# EIT_Teensy_VCCS.net
KiCad netlist of a schematic drawn in Altium Designer
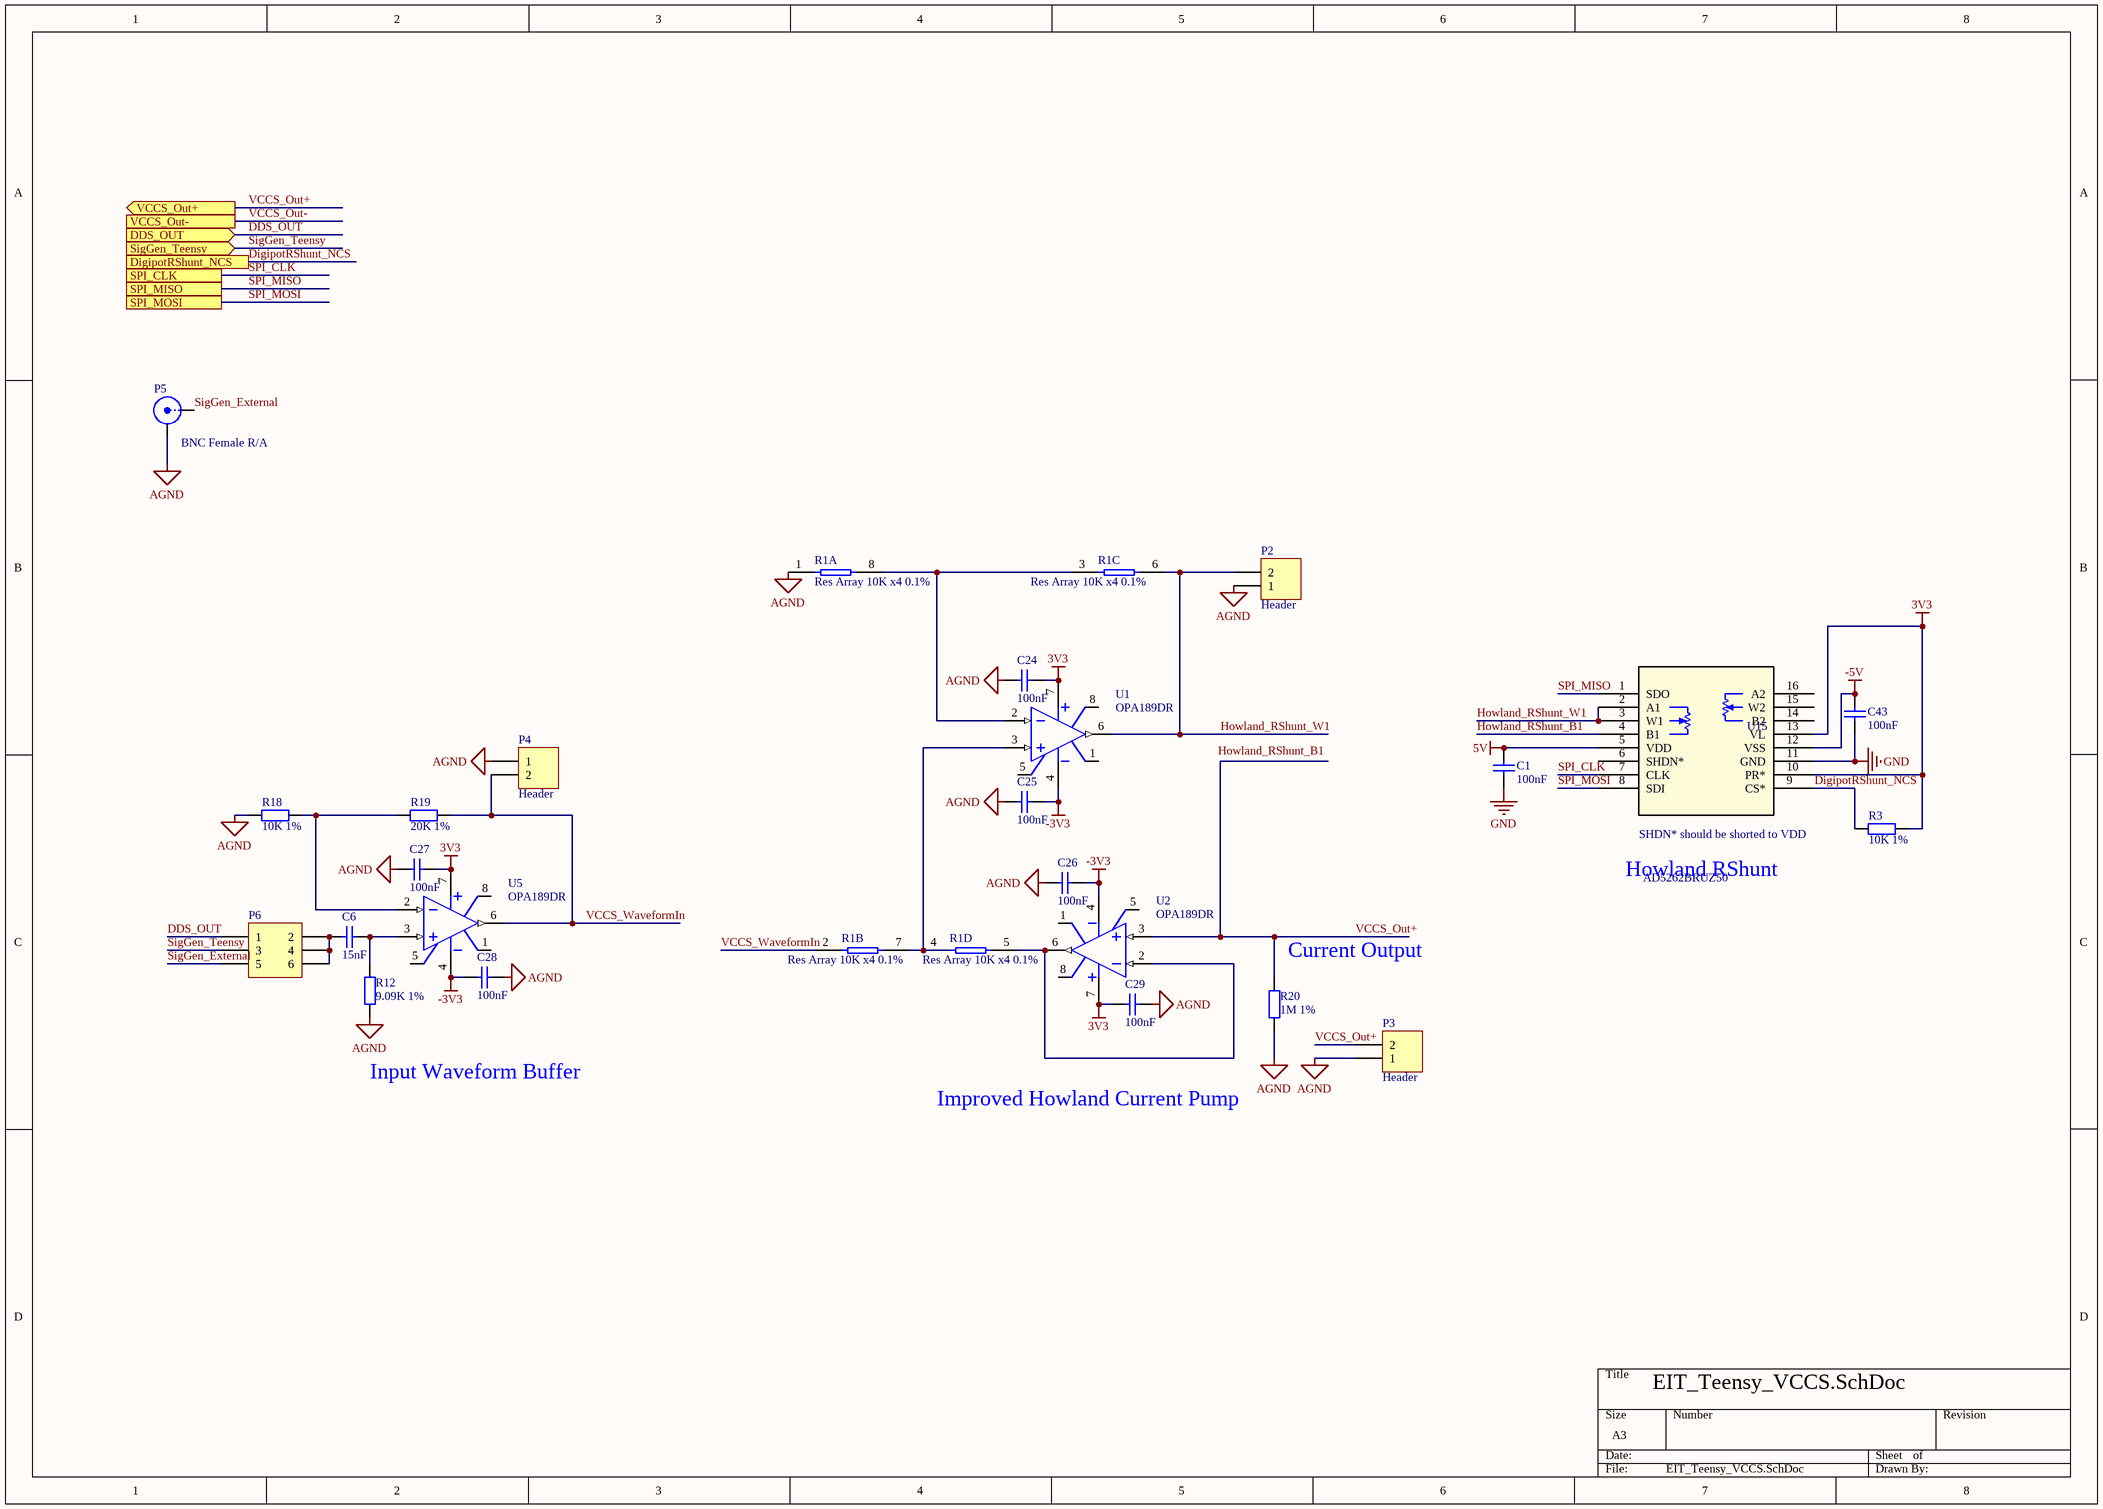
[diagram p0: EIT_Teensy_VCCS.SchDoc]

(export (version "E")
  (design (tool "Eeschema 10.0.6"))
  (components
    (comp (ref "C1")
      (value "100nF")
      (footprint "0603 CAP")
      (description "Multi Layer Ceramic Capacitor (MLCC) / Cap Ceramic 0.1uF 50V X7R 10% Pad SMD 0603 125°C T/R")
      (fields
        (field (name "MANUFACTURER") "Samsung")
        (field (name "MANUFACTURER PART NUMBER") "CL10B104KB8NNNC")
      )
      (libsource (lib "EitLib") (part "Cap 0603 100nF 10% 50V"))
    )
    (comp (ref "C6")
      (value "15nF")
      (footprint "0603 CAP")
      (description "Cap Ceramic 0.015uF 50V X7R 10% SMD 0603 125C T/R")
      (fields
        (field (name "MANUFACTURER") "Yageo")
        (field (name "MANUFACTURER PART NUMBER") "CC0603KRX7R9BB153")
      )
      (libsource (lib "EitLib") (part "Cap 0603 15nF 10% 50V"))
    )
    (comp (ref "C24")
      (value "100nF")
      (footprint "0603 CAP")
      (description "Multi Layer Ceramic Capacitor (MLCC) / Cap Ceramic 0.1uF 50V X7R 10% Pad SMD 0603 125°C T/R")
      (fields
        (field (name "MANUFACTURER") "Samsung")
        (field (name "MANUFACTURER PART NUMBER") "CL10B104KB8NNNC")
      )
      (libsource (lib "EitLib") (part "Cap 0603 100nF 10% 50V"))
    )
    (comp (ref "C25")
      (value "100nF")
      (footprint "0603 CAP")
      (description "Multi Layer Ceramic Capacitor (MLCC) / Cap Ceramic 0.1uF 50V X7R 10% Pad SMD 0603 125°C T/R")
      (fields
        (field (name "MANUFACTURER") "Samsung")
        (field (name "MANUFACTURER PART NUMBER") "CL10B104KB8NNNC")
      )
      (libsource (lib "EitLib") (part "Cap 0603 100nF 10% 50V"))
    )
    (comp (ref "C26")
      (value "100nF")
      (footprint "0603 CAP")
      (description "Multi Layer Ceramic Capacitor (MLCC) / Cap Ceramic 0.1uF 50V X7R 10% Pad SMD 0603 125°C T/R")
      (fields
        (field (name "MANUFACTURER") "Samsung")
        (field (name "MANUFACTURER PART NUMBER") "CL10B104KB8NNNC")
      )
      (libsource (lib "EitLib") (part "Cap 0603 100nF 10% 50V"))
    )
    (comp (ref "C27")
      (value "100nF")
      (footprint "0603 CAP")
      (description "Multi Layer Ceramic Capacitor (MLCC) / Cap Ceramic 0.1uF 50V X7R 10% Pad SMD 0603 125°C T/R")
      (fields
        (field (name "MANUFACTURER") "Samsung")
        (field (name "MANUFACTURER PART NUMBER") "CL10B104KB8NNNC")
      )
      (libsource (lib "EitLib") (part "Cap 0603 100nF 10% 50V"))
    )
    (comp (ref "C28")
      (value "100nF")
      (footprint "0603 CAP")
      (description "Multi Layer Ceramic Capacitor (MLCC) / Cap Ceramic 0.1uF 50V X7R 10% Pad SMD 0603 125°C T/R")
      (fields
        (field (name "MANUFACTURER") "Samsung")
        (field (name "MANUFACTURER PART NUMBER") "CL10B104KB8NNNC")
      )
      (libsource (lib "EitLib") (part "Cap 0603 100nF 10% 50V"))
    )
    (comp (ref "C29")
      (value "100nF")
      (footprint "0603 CAP")
      (description "Multi Layer Ceramic Capacitor (MLCC) / Cap Ceramic 0.1uF 50V X7R 10% Pad SMD 0603 125°C T/R")
      (fields
        (field (name "MANUFACTURER") "Samsung")
        (field (name "MANUFACTURER PART NUMBER") "CL10B104KB8NNNC")
      )
      (libsource (lib "EitLib") (part "Cap 0603 100nF 10% 50V"))
    )
    (comp (ref "C43")
      (value "100nF")
      (footprint "0603 CAP")
      (description "Multi Layer Ceramic Capacitor (MLCC) / Cap Ceramic 0.1uF 50V X7R 10% Pad SMD 0603 125°C T/R")
      (fields
        (field (name "MANUFACTURER") "Samsung")
        (field (name "MANUFACTURER PART NUMBER") "CL10B104KB8NNNC")
      )
      (libsource (lib "EitLib") (part "Cap 0603 100nF 10% 50V"))
    )
    (comp (ref "P2")
      (value "Header")
      (footprint "HEADER 2.54MM 2X1 MALE")
      (description "CONN HEADER VERT 2POS 2.54MM")
      (fields
        (field (name "MANUFACTURER") "Sullins")
        (field (name "MANUFACTURER PART NUMBER") "PRPC002SAAN-RC")
      )
      (libsource (lib "EitLib") (part "Header 2x1 2.54mm T/H Male"))
    )
    (comp (ref "P3")
      (value "Header")
      (footprint "HEADER 2.54MM 2X1 MALE")
      (description "CONN HEADER VERT 2POS 2.54MM")
      (fields
        (field (name "MANUFACTURER") "Sullins")
        (field (name "MANUFACTURER PART NUMBER") "PRPC002SAAN-RC")
      )
      (libsource (lib "EitLib") (part "Header 2x1 2.54mm T/H Male"))
    )
    (comp (ref "P4")
      (value "Header")
      (footprint "HEADER 2.54MM 2X1 MALE")
      (description "CONN HEADER VERT 2POS 2.54MM")
      (fields
        (field (name "MANUFACTURER") "Sullins")
        (field (name "MANUFACTURER PART NUMBER") "PRPC002SAAN-RC")
      )
      (libsource (lib "") (part "Header 2x1 2.54mm T/H Male_1"))
    )
    (comp (ref "P5")
      (value "BNC Female R/A")
      (footprint "BNC_RA CON")
      (description "Conn ZDC/BNC RCP 0Hz to 4GHz 50Ohm Solder RA Thru-Hole Gold Over Nickel Over Copper Individual")
      (fields
        (field (name "MANUFACTURER") "TE Connectivity")
        (field (name "MANUFACTURER PART NUMBER") "1-1337543-0")
      )
      (libsource (lib "EitLib") (part "Jack BNC Female T/H R/A TE"))
    )
    (comp (ref "P6")
      (value "Header 3X2")
      (footprint "HDR2X3 Male 2.54mm")
      (description "Header, 3-Pin, Dual row")
      (libsource (lib "EitLib") (part "Header 3X2 2.54mm Male"))
    )
    (comp (ref "R1")
      (value "Res Array 10K x4 0.1%")
      (footprint "8-SOIC")
      (fields
        (field (name "MANUFACTURER") "Vishay Dale Thin Film")
        (field (name "MANUFACTURER PART NUMBER") "ORNTA1002AT1")
        (field (name "TOLERANCE") "0.1%")
      )
      (libsource (lib "EitLib") (part "Res Array 10K x4 0.1%"))
    )
    (comp (ref "R3")
      (value "10K 1%")
      (footprint "0603 RES")
      (description "Res General Purpose Thick Film 0603 10K Ohm 1% 1/10W ±100ppm/°C Molded SMD Paper T/R")
      (fields
        (field (name "MANUFACTURER") "Yageo")
        (field (name "MANUFACTURER PART NUMBER") "RC0603FR-0710KL")
      )
      (libsource (lib "") (part "Res 0603 10K 1%_1"))
    )
    (comp (ref "R12")
      (value "9.09K 1%")
      (footprint "0603 RES")
      (description "Res Thick Film 0603 90.9K Ohm 1% 0.1W(1/10W) ±100ppm/C Epoxy SMD T/R")
      (fields
        (field (name "MANUFACTURER") "Yageo")
        (field (name "MANUFACTURER PART NUMBER") "RC0603FR-0790K9L")
      )
      (libsource (lib "EitLib") (part "Res 0603 9.09K 1%"))
    )
    (comp (ref "R18")
      (value "10K 1%")
      (footprint "0603 RES")
      (description "Res General Purpose Thick Film 0603 10K Ohm 1% 1/10W ±100ppm/°C Molded SMD Paper T/R")
      (fields
        (field (name "MANUFACTURER") "Yageo")
        (field (name "MANUFACTURER PART NUMBER") "RC0603FR-0710KL")
      )
      (libsource (lib "EitLib") (part "Res 0603 10K 1%"))
    )
    (comp (ref "R19")
      (value "20K 1%")
      (footprint "0603 RES")
      (description "Res General Purpose Thick Film 0603 20K Ohm 1% 1/10W ±100ppm/°C Molded SMD Paper T/R")
      (fields
        (field (name "MANUFACTURER") "Yageo")
        (field (name "MANUFACTURER PART NUMBER") "RC0603FR-0720KL")
      )
      (libsource (lib "EitLib") (part "Res 0603 20K 1%"))
    )
    (comp (ref "R20")
      (value "1M 1%")
      (footprint "0603 RES")
      (description "Yageo RC Series Thick Film Surface Mount Resistor 0603 Case 1M 1% 0.1W 100ppm/C")
      (fields
        (field (name "MANUFACTURER") "Yageo")
        (field (name "MANUFACTURER PART NUMBER") "RC0603FR-071ML")
      )
      (libsource (lib "EitLib") (part "Res 0603 1M 1%"))
    )
    (comp (ref "U1")
      (value "OPA189DR")
      (footprint "8-SOIC")
      (description "36V ZERO DRIFT OP-AMP")
      (fields
        (field (name "MANUFACTURER") "Texas Instruments")
        (field (name "MANUFACTURER PART NUMBER") "OPA189IDR")
      )
      (libsource (lib "EitLib") (part "OpAmp OPA189DR"))
    )
    (comp (ref "U2")
      (value "OPA189DR")
      (footprint "8-SOIC")
      (description "36V ZERO DRIFT OP-AMP")
      (fields
        (field (name "MANUFACTURER") "Texas Instruments")
        (field (name "MANUFACTURER PART NUMBER") "OPA189IDR")
      )
      (libsource (lib "EitLib") (part "OpAmp OPA189DR"))
    )
    (comp (ref "U5")
      (value "OPA189DR")
      (footprint "8-SOIC")
      (description "36V ZERO DRIFT OP-AMP")
      (fields
        (field (name "MANUFACTURER") "Texas Instruments")
        (field (name "MANUFACTURER PART NUMBER") "OPA189IDR")
      )
      (libsource (lib "EitLib") (part "OpAmp OPA189DR"))
    )
    (comp (ref "U15")
      (value "AD5262BRUZ50")
      (description "Digital Potentiometer, 2 Func, 50000ohm, 3-wire Serial Control Interface, 256 Positions, PDSO16")
      (fields (field (name "MANUFACTURER") "Analog Devices"))
      (libsource (lib "EitLib") (part "AD5262BRUZ50"))
    )
  )
  (nets
    (net (code "1") (name "-3V3") (class "Default")
      (node (ref "C25") (pin "2") (pinfunction "2_2") (pintype "passive"))
      (node (ref "C26") (pin "2") (pinfunction "2_2") (pintype "passive"))
      (node (ref "C28") (pin "1") (pinfunction "1_1") (pintype "passive"))
      (node (ref "U1") (pin "4") (pinfunction "V-_4") (pintype "power_in"))
      (node (ref "U2") (pin "4") (pinfunction "V-_4") (pintype "power_in"))
      (node (ref "U5") (pin "4") (pinfunction "V-_4") (pintype "power_in"))
    )
    (net (code "2") (name "-5V") (class "Default")
      (node (ref "C43") (pin "2") (pinfunction "2_2") (pintype "passive"))
      (node (ref "U15") (pin "12") (pinfunction "VSS_12") (pintype "power_in"))
    )
    (net (code "3") (name "/DDS_OUT") (class "Default")
      (node (ref "P6") (pin "1") (pinfunction "1_1") (pintype "passive"))
    )
    (net (code "4") (name "/DigipotRShunt_NCS") (class "Default")
      (node (ref "R3") (pin "2") (pinfunction "2_2") (pintype "passive"))
      (node (ref "U15") (pin "9") (pinfunction "CS*_9") (pintype "passive"))
    )
    (net (code "5") (name "/Howland_RShunt_B1") (class "Default")
      (node (ref "U15") (pin "4") (pinfunction "B1_4") (pintype "passive"))
    )
    (net (code "6") (name "/Howland_RShunt_W1") (class "Default")
      (node (ref "P2") (pin "2") (pinfunction "2_2") (pintype "passive"))
      (node (ref "R1") (pin "6") (pinfunction "6_6") (pintype "passive"))
      (node (ref "U1") (pin "6") (pinfunction "OUT_6") (pintype "output"))
      (node (ref "U15") (pin "2") (pinfunction "A1_2") (pintype "passive"))
      (node (ref "U15") (pin "3") (pinfunction "W1_3") (pintype "passive"))
    )
    (net (code "7") (name "/SPI_CLK") (class "Default")
      (node (ref "U15") (pin "7") (pinfunction "CLK_7") (pintype "passive"))
    )
    (net (code "8") (name "/SPI_MISO") (class "Default")
      (node (ref "U15") (pin "1") (pinfunction "SDO_1") (pintype "passive"))
    )
    (net (code "9") (name "/SPI_MOSI") (class "Default")
      (node (ref "U15") (pin "8") (pinfunction "SDI_8") (pintype "passive"))
    )
    (net (code "10") (name "/SigGen_External") (class "Default")
      (node (ref "P5") (pin "1") (pinfunction "X_1") (pintype "passive"))
      (node (ref "P6") (pin "5") (pinfunction "5_5") (pintype "passive"))
    )
    (net (code "11") (name "/SigGen_Teensy") (class "Default")
      (node (ref "P6") (pin "3") (pinfunction "3_3") (pintype "passive"))
    )
    (net (code "12") (name "/VCCS_Out+") (class "Default")
      (node (ref "P3") (pin "2") (pinfunction "2_2") (pintype "passive"))
      (node (ref "R20") (pin "1") (pinfunction "1_1") (pintype "passive"))
      (node (ref "U2") (pin "3") (pinfunction "IN+_3") (pintype "input"))
    )
    (net (code "14") (name "/VCCS_WaveformIn") (class "Default")
      (node (ref "P4") (pin "2") (pinfunction "2_2") (pintype "passive"))
      (node (ref "R1") (pin "2") (pinfunction "2_2") (pintype "passive"))
      (node (ref "R19") (pin "2") (pinfunction "2_2") (pintype "passive"))
      (node (ref "U5") (pin "6") (pinfunction "OUT_6") (pintype "output"))
    )
    (net (code "15") (name "3V3") (class "Default")
      (node (ref "C24") (pin "2") (pinfunction "2_2") (pintype "passive"))
      (node (ref "C27") (pin "2") (pinfunction "2_2") (pintype "passive"))
      (node (ref "C29") (pin "2") (pinfunction "2_2") (pintype "passive"))
      (node (ref "R3") (pin "1") (pinfunction "1_1") (pintype "passive"))
      (node (ref "U1") (pin "7") (pinfunction "V+_7") (pintype "power_in"))
      (node (ref "U15") (pin "10") (pinfunction "PR*_10") (pintype "passive"))
      (node (ref "U15") (pin "13") (pinfunction "VL_13") (pintype "power_in"))
      (node (ref "U2") (pin "7") (pinfunction "V+_7") (pintype "power_in"))
      (node (ref "U5") (pin "7") (pinfunction "V+_7") (pintype "power_in"))
    )
    (net (code "16") (name "5V") (class "Default")
      (node (ref "C1") (pin "2") (pinfunction "2_2") (pintype "passive"))
      (node (ref "U15") (pin "5") (pinfunction "VDD_5") (pintype "power_in"))
    )
    (net (code "17") (name "AGND") (class "Default")
      (node (ref "C24") (pin "1") (pinfunction "1_1") (pintype "passive"))
      (node (ref "C25") (pin "1") (pinfunction "1_1") (pintype "passive"))
      (node (ref "C26") (pin "1") (pinfunction "1_1") (pintype "passive"))
      (node (ref "C27") (pin "1") (pinfunction "1_1") (pintype "passive"))
      (node (ref "C28") (pin "2") (pinfunction "2_2") (pintype "passive"))
      (node (ref "C29") (pin "1") (pinfunction "1_1") (pintype "passive"))
      (node (ref "P2") (pin "1") (pinfunction "1_1") (pintype "passive"))
      (node (ref "P3") (pin "1") (pinfunction "1_1") (pintype "passive"))
      (node (ref "P4") (pin "1") (pinfunction "1_1") (pintype "passive"))
      (node (ref "P5") (pin "2") (pinfunction "Y_2") (pintype "passive"))
      (node (ref "R1") (pin "1") (pinfunction "1_1") (pintype "passive"))
      (node (ref "R12") (pin "1") (pinfunction "1_1") (pintype "passive"))
      (node (ref "R18") (pin "1") (pinfunction "1_1") (pintype "passive"))
      (node (ref "R20") (pin "2") (pinfunction "2_2") (pintype "passive"))
    )
    (net (code "18") (name "GND") (class "Default")
      (node (ref "C1") (pin "1") (pinfunction "1_1") (pintype "passive"))
      (node (ref "C43") (pin "1") (pinfunction "1_1") (pintype "passive"))
      (node (ref "U15") (pin "11") (pinfunction "GND_11") (pintype "passive"))
    )
    (net (code "19") (name "Net-(C6-Pad1)") (class "Default")
      (node (ref "C6") (pin "1") (pinfunction "1_1") (pintype "passive"))
      (node (ref "P6") (pin "2") (pinfunction "2_2") (pintype "passive"))
      (node (ref "P6") (pin "4") (pinfunction "4_4") (pintype "passive"))
      (node (ref "P6") (pin "6") (pinfunction "6_6") (pintype "passive"))
    )
    (net (code "20") (name "Net-(U1-IN+)") (class "Default")
      (node (ref "R1") (pin "4") (pinfunction "4_4") (pintype "passive"))
      (node (ref "R1") (pin "7") (pinfunction "7_7") (pintype "passive"))
      (node (ref "U1") (pin "3") (pinfunction "IN+_3") (pintype "input"))
    )
    (net (code "21") (name "Net-(U1-IN-)") (class "Default")
      (node (ref "R1") (pin "3") (pinfunction "3_3") (pintype "passive"))
      (node (ref "R1") (pin "8") (pinfunction "8_8") (pintype "passive"))
      (node (ref "U1") (pin "2") (pinfunction "IN-_2") (pintype "input"))
    )
    (net (code "22") (name "Net-(U2-IN-)") (class "Default")
      (node (ref "R1") (pin "5") (pinfunction "5_5") (pintype "passive"))
      (node (ref "U2") (pin "2") (pinfunction "IN-_2") (pintype "input"))
      (node (ref "U2") (pin "6") (pinfunction "OUT_6") (pintype "output"))
    )
    (net (code "23") (name "Net-(U5-IN+)") (class "Default")
      (node (ref "C6") (pin "2") (pinfunction "2_2") (pintype "passive"))
      (node (ref "R12") (pin "2") (pinfunction "2_2") (pintype "passive"))
      (node (ref "U5") (pin "3") (pinfunction "IN+_3") (pintype "input"))
    )
    (net (code "24") (name "Net-(U5-IN-)") (class "Default")
      (node (ref "R18") (pin "2") (pinfunction "2_2") (pintype "passive"))
      (node (ref "R19") (pin "1") (pinfunction "1_1") (pintype "passive"))
      (node (ref "U5") (pin "2") (pinfunction "IN-_2") (pintype "input"))
    )
    (net (code "25") (name "unconnected-(U1-OS_NUL-Pad1)") (class "Default")
      (node (ref "U1") (pin "1") (pinfunction "OS_NUL_1") (pintype "passive"))
    )
    (net (code "26") (name "unconnected-(U1-OS_NUL-Pad5)") (class "Default")
      (node (ref "U1") (pin "5") (pinfunction "OS_NUL_5") (pintype "passive"))
    )
    (net (code "27") (name "unconnected-(U1-TAB-Pad8)") (class "Default")
      (node (ref "U1") (pin "8") (pinfunction "TAB_8") (pintype "passive"))
    )
    (net (code "28") (name "unconnected-(U2-OS_NUL-Pad1)") (class "Default")
      (node (ref "U2") (pin "1") (pinfunction "OS_NUL_1") (pintype "passive"))
    )
    (net (code "29") (name "unconnected-(U2-OS_NUL-Pad5)") (class "Default")
      (node (ref "U2") (pin "5") (pinfunction "OS_NUL_5") (pintype "passive"))
    )
    (net (code "30") (name "unconnected-(U2-TAB-Pad8)") (class "Default")
      (node (ref "U2") (pin "8") (pinfunction "TAB_8") (pintype "passive"))
    )
    (net (code "31") (name "unconnected-(U5-OS_NUL-Pad1)") (class "Default")
      (node (ref "U5") (pin "1") (pinfunction "OS_NUL_1") (pintype "passive"))
    )
    (net (code "32") (name "unconnected-(U5-OS_NUL-Pad5)") (class "Default")
      (node (ref "U5") (pin "5") (pinfunction "OS_NUL_5") (pintype "passive"))
    )
    (net (code "33") (name "unconnected-(U5-TAB-Pad8)") (class "Default")
      (node (ref "U5") (pin "8") (pinfunction "TAB_8") (pintype "passive"))
    )
    (net (code "34") (name "unconnected-(U15-A2-Pad16)") (class "Default")
      (node (ref "U15") (pin "16") (pinfunction "A2_16") (pintype "passive"))
    )
    (net (code "35") (name "unconnected-(U15-B2-Pad14)") (class "Default")
      (node (ref "U15") (pin "14") (pinfunction "B2_14") (pintype "passive"))
    )
    (net (code "36") (name "unconnected-(U15-SHDN*-Pad6)") (class "Default")
      (node (ref "U15") (pin "6") (pinfunction "SHDN*_6") (pintype "passive"))
    )
    (net (code "37") (name "unconnected-(U15-W2-Pad15)") (class "Default")
      (node (ref "U15") (pin "15") (pinfunction "W2_15") (pintype "passive"))
    )
  )
)
